# Amplifier.net
KiCad netlist of a schematic drawn in Altium Designer
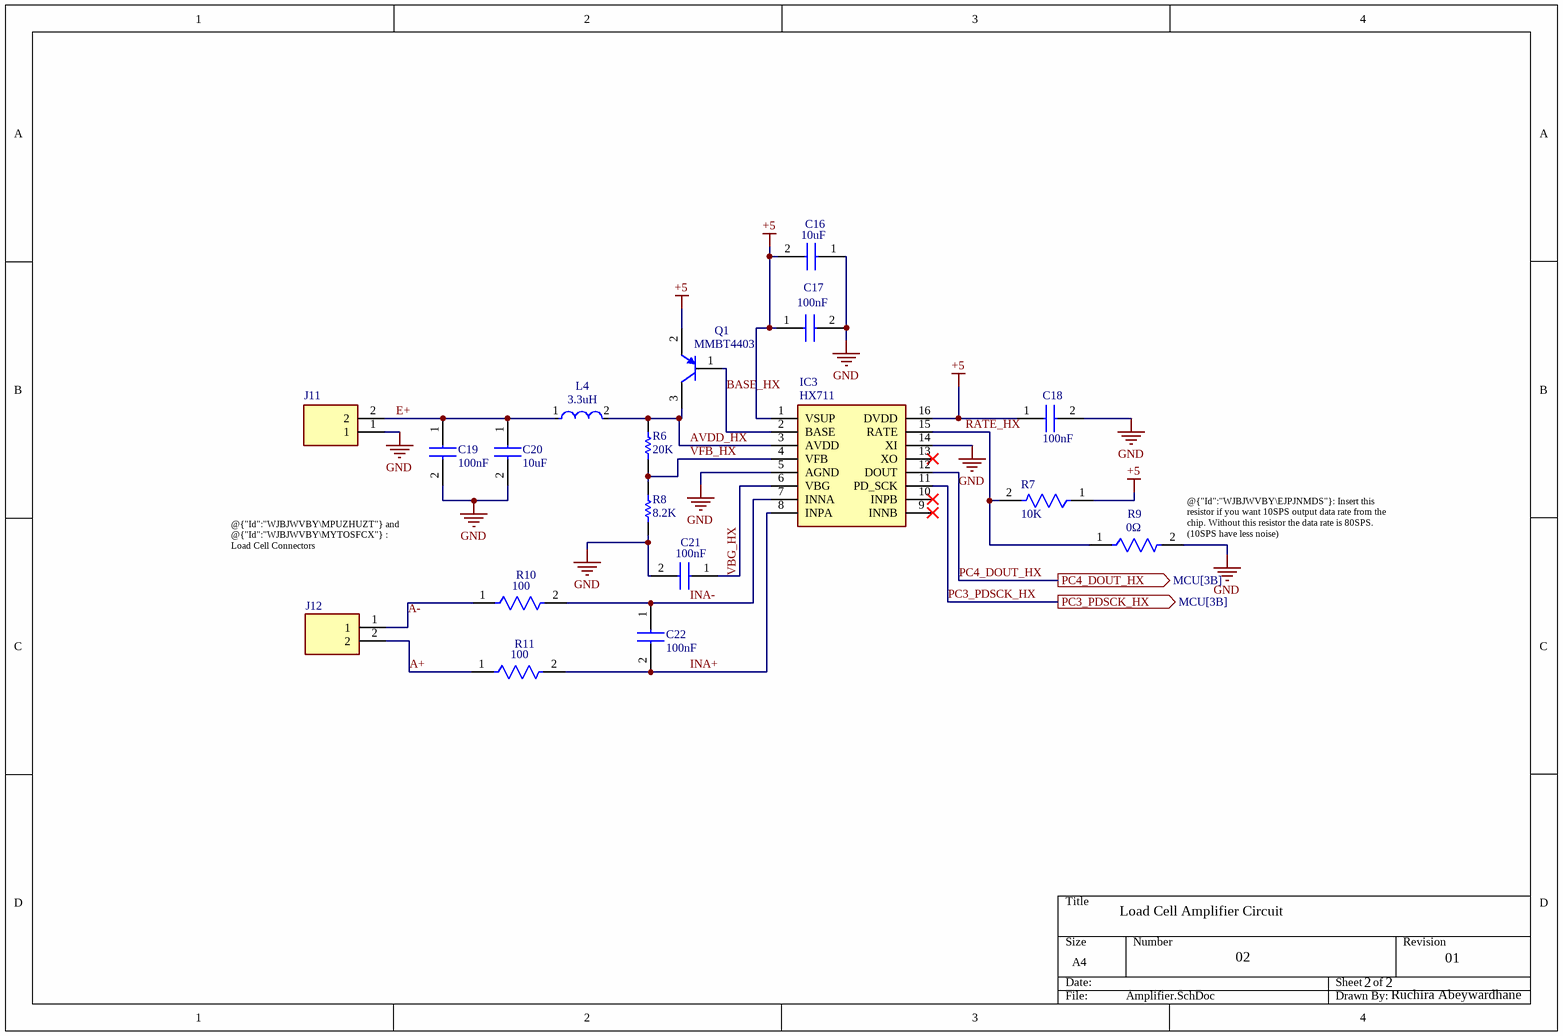
[diagram p0: Amplifier.SchDoc]

(export (version "E")
  (design (tool "Eeschema 10.0.6"))
  (components
    (comp (ref "C16")
      (value "10uF")
      (footprint "SamacSys:C0805")
      (description "Capacitor")
      (fields
        (field (name "MANUFACTURER_PART_NUMBER") "C0805C106K4PAC7210")
        (field (name "MOUSER PART NUMBER") "80-C0805C106K4P7210")
      )
      (libsource (lib "*") (part "C0805C106K4PAC7210"))
    )
    (comp (ref "C17")
      (value "100nF")
      (footprint "SamacSys:C0805")
      (description "Capacitor")
      (fields (field (name "MANUFACTURER_PART_NUMBER") "C0805Y104J3RACTU"))
      (libsource (lib "*") (part "C0805Y104J3RACTU"))
    )
    (comp (ref "C18")
      (value "100nF")
      (footprint "SamacSys:C0805")
      (description "Capacitor")
      (fields (field (name "MANUFACTURER_PART_NUMBER") "C0805Y104J3RACTU"))
      (libsource (lib "*") (part "C0805Y104J3RACTU"))
    )
    (comp (ref "C19")
      (value "100nF")
      (footprint "SamacSys:C0805")
      (description "Capacitor")
      (fields (field (name "MANUFACTURER_PART_NUMBER") "C0805Y104J3RACTU"))
      (libsource (lib "*") (part "C0805Y104J3RACTU"))
    )
    (comp (ref "C20")
      (value "10uF")
      (footprint "SamacSys:C0805")
      (description "Capacitor")
      (fields
        (field (name "MANUFACTURER_PART_NUMBER") "C0805C106K4PAC7210")
        (field (name "MOUSER PART NUMBER") "80-C0805C106K4P7210")
      )
      (libsource (lib "*") (part "C0805C106K4PAC7210"))
    )
    (comp (ref "C21")
      (value "100nF")
      (footprint "SamacSys:C0805")
      (description "Capacitor")
      (fields (field (name "MANUFACTURER_PART_NUMBER") "C0805Y104J3RACTU"))
      (libsource (lib "*") (part "C0805Y104J3RACTU"))
    )
    (comp (ref "C22")
      (value "100nF")
      (footprint "SamacSys:C0805")
      (description "Capacitor")
      (fields (field (name "MANUFACTURER_PART_NUMBER") "C0805Y104J3RACTU"))
      (libsource (lib "*") (part "C0805Y104J3RACTU"))
    )
    (comp (ref "IC3")
      (value "HX711")
      (footprint "SamacSys:SOIC127P600X160-16N")
      (description "Integrated Circuit")
      (libsource (lib "*") (part "HX711"))
    )
    (comp (ref "J11")
      (value "1727010")
      (footprint "SamacSys:1727010")
      (description "Connector")
      (fields (field (name "MOUSER PART NUMBER") "651-1727010"))
      (libsource (lib "") (part "1727010_1"))
    )
    (comp (ref "J12")
      (value "1727010")
      (footprint "SamacSys:1727010")
      (description "Connector")
      (fields (field (name "MOUSER PART NUMBER") "651-1727010"))
      (libsource (lib "*") (part "1727010"))
    )
    (comp (ref "L4")
      (value "3.3uH")
      (footprint "FP-MLZ2012-0_85-IPC_C")
      (description "Shielded Multilayer Inductor 3.3uH ±20% 450mA 442mΩ AEC-Q200 SMD 0805")
      (fields (field (name "TOLERANCE") "20%") (field (name "Comment") "MLZ2012A3R3WTD25"))
      (libsource (lib "Altium Content Vault") (part "725321dda6339637d4d059423bc1c3c"))
    )
    (comp (ref "Q1")
      (value "MMBT4403M3T5G")
      (footprint "ONSC-SOT-723-3-631AA-01_C_V")
      (description "PNP Switching Transistor, 3-Pin SOT-723, Pb-Free, Tape and Reel")
      (fields (field (name "MANUFACTURER") "On Semiconductor") (field (name "MODEL") "MMBT4403"))
      (libsource (lib "Altium Content Vault") (part "ONSC-PNP-B1E2C3-3"))
    )
    (comp (ref "R6")
      (value "20K")
      (footprint "RESC2013X60X30LL20T20")
      (fields (field (name "MANUFACTURER") "KOA Speer") (field (name "PART NUMBER") "RK73H2ATTD2002F"))
      (libsource (lib "Altium Content Vault") (part "RES"))
    )
    (comp (ref "R7")
      (value "10K")
      (footprint "FP-RK73H2A-IPC_C")
      (description "10kΩ ±1% 0.25W Chip Resistor 0805 Thick Film AEC-Q200 Qualified")
      (fields (field (name "TOLERANCE") "1%") (field (name "Comment") "RK73H2ATTED1002F"))
      (libsource (lib "Altium Content Vault") (part "1029c3af85768c4190bb7ad29bc67b5"))
    )
    (comp (ref "R8")
      (value "8.2K")
      (footprint "RESC2013X60X30NL20T20")
      (fields (field (name "PART NUMBER") "RK73H2ATTD8201F") (field (name "MANUFACTURER") "KOA Speer"))
      (libsource (lib "Altium Content Vault") (part "RES"))
    )
    (comp (ref "R9")
      (value "RCC08050000Z0EA")
      (footprint "FP-RCC0805-e3-MFG")
      (description "RCC08050000Z0EA Res Thick Film 0805 0 Ohm Conformal Coated Pad SMD Automotive AEC-Q200 T/R")
      (fields (field (name "RESISTANCE") "0Ω"))
      (libsource (lib "Altium Content Vault") (part "1029c3af85768c4190bb7ad29bc67b5"))
    )
    (comp (ref "R10")
      (value "100")
      (footprint "FP-RK73H2A-IPC_A")
      (description "100Ω ±1% 0.25W Chip Resistor 0805 Thick Film AEC-Q200 Qualified")
      (fields (field (name "TOLERANCE") "1%") (field (name "Comment") "RK73H2ATTED1000F"))
      (libsource (lib "Altium Content Vault") (part "1029c3af85768c4190bb7ad29bc67b5"))
    )
    (comp (ref "R11")
      (value "100")
      (footprint "FP-RK73H2A-IPC_A")
      (description "100Ω ±1% 0.25W Chip Resistor 0805 Thick Film AEC-Q200 Qualified")
      (fields (field (name "TOLERANCE") "1%") (field (name "Comment") "RK73H2ATTED1000F"))
      (libsource (lib "Altium Content Vault") (part "1029c3af85768c4190bb7ad29bc67b5"))
    )
  )
  (nets
    (net (code "1") (name "+5") (class "Default")
      (node (ref "C16") (pin "2") (pinfunction "2_2") (pintype "passive"))
      (node (ref "C17") (pin "1") (pinfunction "1_1") (pintype "passive"))
      (node (ref "C18") (pin "1") (pinfunction "1_1") (pintype "passive"))
      (node (ref "IC3") (pin "1") (pinfunction "VSUP_1") (pintype "passive"))
      (node (ref "IC3") (pin "16") (pinfunction "DVDD_16") (pintype "passive"))
      (node (ref "Q1") (pin "2") (pinfunction "E_2") (pintype "passive"))
      (node (ref "R7") (pin "1") (pinfunction "1_1") (pintype "passive"))
    )
    (net (code "2") (name "/A+") (class "Default")
      (node (ref "J12") (pin "2") (pinfunction "2_2") (pintype "passive"))
      (node (ref "R11") (pin "1") (pinfunction "1_1") (pintype "passive"))
    )
    (net (code "3") (name "/A-") (class "Default")
      (node (ref "J12") (pin "1") (pinfunction "1_1") (pintype "passive"))
      (node (ref "R10") (pin "1") (pinfunction "1_1") (pintype "passive"))
    )
    (net (code "4") (name "/AVDD_HX") (class "Default")
      (node (ref "IC3") (pin "3") (pinfunction "AVDD_3") (pintype "passive"))
      (node (ref "L4") (pin "2") (pinfunction "2_2") (pintype "passive"))
      (node (ref "Q1") (pin "3") (pinfunction "C_3") (pintype "passive"))
      (node (ref "R6") (pin "2") (pinfunction "2_2") (pintype "passive"))
    )
    (net (code "5") (name "/BASE_HX") (class "Default")
      (node (ref "IC3") (pin "2") (pinfunction "BASE_2") (pintype "passive"))
      (node (ref "Q1") (pin "1") (pinfunction "B_1") (pintype "passive"))
    )
    (net (code "6") (name "/E+") (class "Default")
      (node (ref "C19") (pin "1") (pinfunction "1_1") (pintype "passive"))
      (node (ref "C20") (pin "1") (pinfunction "1_1") (pintype "passive"))
      (node (ref "J11") (pin "2") (pinfunction "2_2") (pintype "passive"))
      (node (ref "L4") (pin "1") (pinfunction "1_1") (pintype "passive"))
    )
    (net (code "7") (name "/INA+") (class "Default")
      (node (ref "C22") (pin "2") (pinfunction "2_2") (pintype "passive"))
      (node (ref "IC3") (pin "8") (pinfunction "INPA_8") (pintype "passive"))
      (node (ref "R11") (pin "2") (pinfunction "2_2") (pintype "passive"))
    )
    (net (code "8") (name "/INA-") (class "Default")
      (node (ref "C22") (pin "1") (pinfunction "1_1") (pintype "passive"))
      (node (ref "IC3") (pin "7") (pinfunction "INNA_7") (pintype "passive"))
      (node (ref "R10") (pin "2") (pinfunction "2_2") (pintype "passive"))
    )
    (net (code "9") (name "/PC3_PDSCK_HX") (class "Default")
      (node (ref "IC3") (pin "11") (pinfunction "PD_SCK_11") (pintype "passive"))
    )
    (net (code "10") (name "/PC4_DOUT_HX") (class "Default")
      (node (ref "IC3") (pin "12") (pinfunction "DOUT_12") (pintype "passive"))
    )
    (net (code "11") (name "/RATE_HX") (class "Default")
      (node (ref "IC3") (pin "15") (pinfunction "RATE_15") (pintype "passive"))
      (node (ref "R7") (pin "2") (pinfunction "2_2") (pintype "passive"))
      (node (ref "R9") (pin "1") (pinfunction "1_1") (pintype "passive"))
    )
    (net (code "12") (name "/VBG_HX") (class "Default")
      (node (ref "C21") (pin "1") (pinfunction "1_1") (pintype "passive"))
      (node (ref "IC3") (pin "6") (pinfunction "VBG_6") (pintype "passive"))
    )
    (net (code "13") (name "/VFB_HX") (class "Default")
      (node (ref "IC3") (pin "4") (pinfunction "VFB_4") (pintype "passive"))
      (node (ref "R6") (pin "1") (pinfunction "1_1") (pintype "passive"))
      (node (ref "R8") (pin "2") (pinfunction "2_2") (pintype "passive"))
    )
    (net (code "14") (name "GND") (class "Default")
      (node (ref "C16") (pin "1") (pinfunction "1_1") (pintype "passive"))
      (node (ref "C17") (pin "2") (pinfunction "2_2") (pintype "passive"))
      (node (ref "C18") (pin "2") (pinfunction "2_2") (pintype "passive"))
      (node (ref "C19") (pin "2") (pinfunction "2_2") (pintype "passive"))
      (node (ref "C20") (pin "2") (pinfunction "2_2") (pintype "passive"))
      (node (ref "C21") (pin "2") (pinfunction "2_2") (pintype "passive"))
      (node (ref "IC3") (pin "14") (pinfunction "XI_14") (pintype "passive"))
      (node (ref "IC3") (pin "5") (pinfunction "AGND_5") (pintype "passive"))
      (node (ref "J11") (pin "1") (pinfunction "1_1") (pintype "passive"))
      (node (ref "R8") (pin "1") (pinfunction "1_1") (pintype "passive"))
      (node (ref "R9") (pin "2") (pinfunction "2_2") (pintype "passive"))
    )
    (net (code "15") (name "unconnected-(IC3-INNB-Pad9)") (class "Default")
      (node (ref "IC3") (pin "9") (pinfunction "INNB_9") (pintype "passive+no_connect"))
    )
    (net (code "16") (name "unconnected-(IC3-INPB-Pad10)") (class "Default")
      (node (ref "IC3") (pin "10") (pinfunction "INPB_10") (pintype "passive+no_connect"))
    )
    (net (code "17") (name "unconnected-(IC3-XO-Pad13)") (class "Default")
      (node (ref "IC3") (pin "13") (pinfunction "XO_13") (pintype "passive+no_connect"))
    )
  )
)
